# CAN485_1_0_0.net
KiCad netlist of a schematic drawn in EAGLE
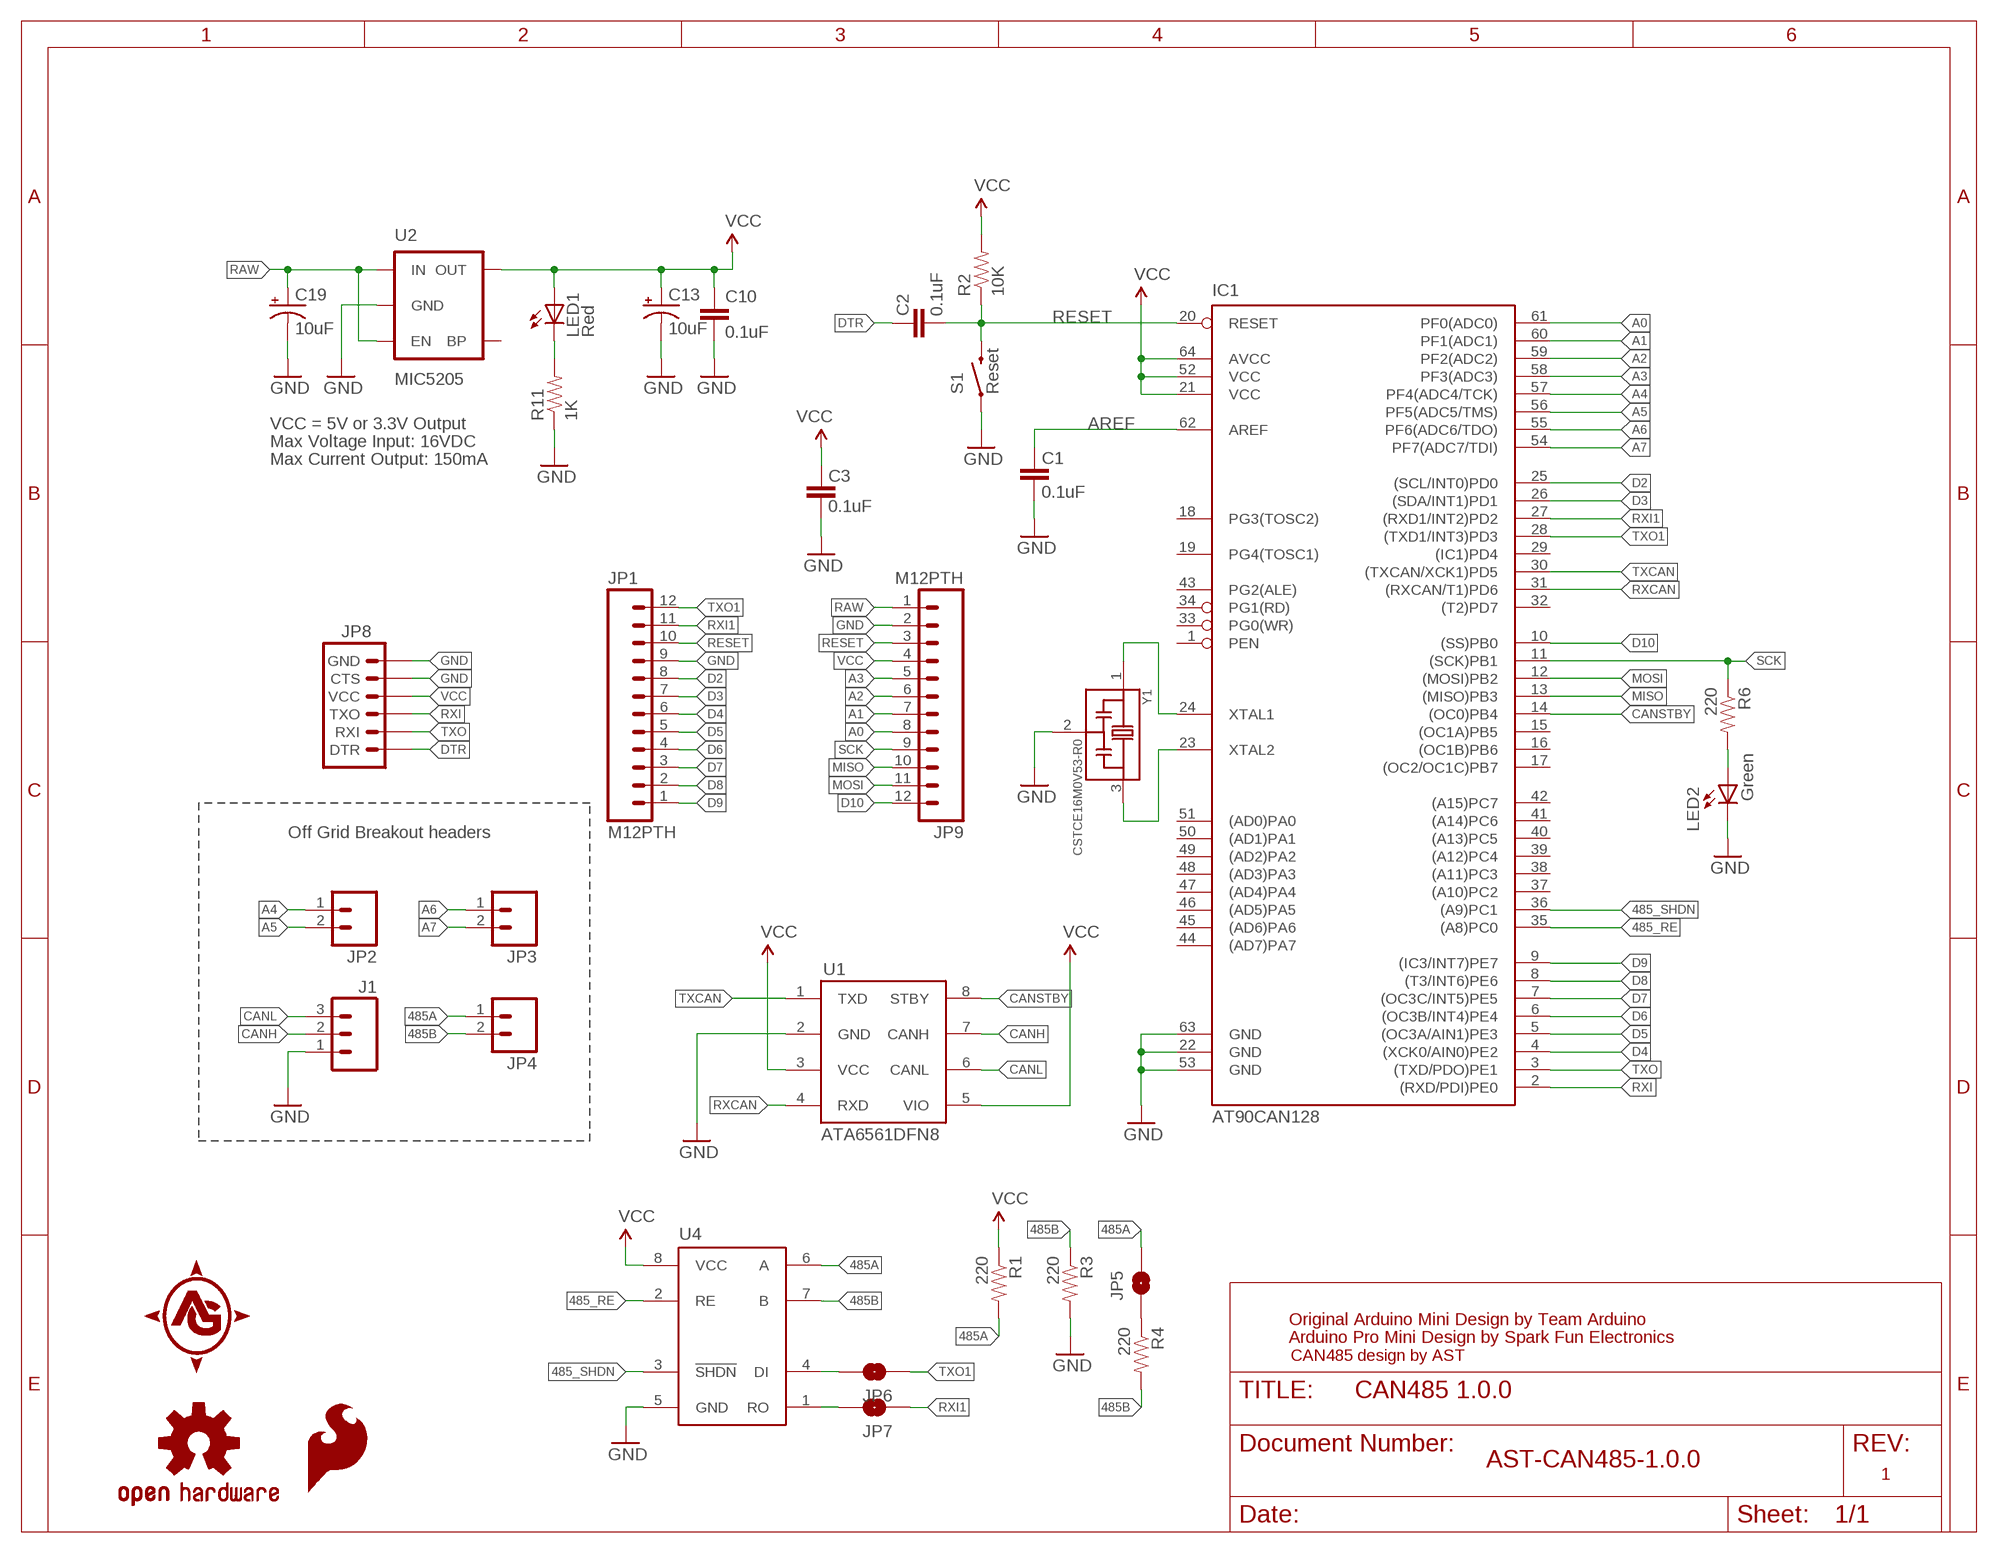
[diagram p0: schematic, sheet 1]

(export (version "E")
  (design (tool "Eeschema 10.0.6"))
  (components
    (comp (ref "C1")
      (value "0.1uF")
      (footprint "eagle-import:0402-CAP")
      (libsource (lib "eagle-import") (part "CAP0402-CAP"))
    )
    (comp (ref "C2")
      (value "0.1uF")
      (footprint "eagle-import:0402-CAP")
      (libsource (lib "eagle-import") (part "CAP0402-CAP"))
    )
    (comp (ref "C3")
      (value "0.1uF")
      (footprint "eagle-import:0402-CAP")
      (libsource (lib "eagle-import") (part "CAP0402-CAP"))
    )
    (comp (ref "C10")
      (value "0.1uF")
      (footprint "eagle-import:0402-CAP")
      (libsource (lib "eagle-import") (part "CAP0402-CAP"))
    )
    (comp (ref "C13")
      (value "10uF")
      (footprint "eagle-import:EIA3216")
      (libsource (lib "eagle-import") (part "CAP_POL1206"))
    )
    (comp (ref "C19")
      (value "10uF")
      (footprint "eagle-import:EIA3216")
      (libsource (lib "eagle-import") (part "CAP_POL1206"))
    )
    (comp (ref "IC1")
      (value "AT90CAN128")
      (footprint "eagle-import:MLF64")
      (fields (field (name "MPN") "ATMEGA64-16MU"))
      (libsource (lib "eagle-import") (part "MEGA64-M"))
    )
    (comp (ref "J1")
      (value "M03PTH")
      (footprint "eagle-import:1X03")
      (libsource (lib "eagle-import") (part "M03PTH"))
    )
    (comp (ref "JP1")
      (value "M12PTH")
      (footprint "eagle-import:1X12")
      (libsource (lib "eagle-import") (part "M12PTH"))
    )
    (comp (ref "JP2")
      (value "M02PTH")
      (footprint "eagle-import:1X02")
      (libsource (lib "eagle-import") (part "M02PTH"))
    )
    (comp (ref "JP3")
      (value "M02PTH")
      (footprint "eagle-import:1X02")
      (libsource (lib "eagle-import") (part "M02PTH"))
    )
    (comp (ref "JP4")
      (value "M02PTH")
      (footprint "eagle-import:1X02")
      (libsource (lib "eagle-import") (part "M02PTH"))
    )
    (comp (ref "JP5")
      (value "JUMPER-PAD-2-NO")
      (footprint "eagle-import:PAD-JUMPER-2-NO_NO_SILK")
      (libsource (lib "eagle-import") (part "JUMPER-PAD-2-NO"))
    )
    (comp (ref "JP6")
      (value "JUMPER-PAD-2-NO")
      (footprint "eagle-import:PAD-JUMPER-2-NO_NO_SILK")
      (libsource (lib "eagle-import") (part "JUMPER-PAD-2-NO"))
    )
    (comp (ref "JP7")
      (value "JUMPER-PAD-2-NO")
      (footprint "eagle-import:PAD-JUMPER-2-NO_NO_SILK")
      (libsource (lib "eagle-import") (part "JUMPER-PAD-2-NO"))
    )
    (comp (ref "JP8")
      (value "ARDUINO_SERIAL_PROGRAMPTH")
      (footprint "eagle-import:1X06")
      (libsource (lib "eagle-import") (part "ARDUINO_SERIAL_PROGRAMPTH"))
    )
    (comp (ref "JP9")
      (value "M12PTH")
      (footprint "eagle-import:1X12")
      (libsource (lib "eagle-import") (part "M12PTH"))
    )
    (comp (ref "LED1")
      (value "Red")
      (footprint "eagle-import:0603-LED-ALT1")
      (libsource (lib "eagle-import") (part "LED"))
    )
    (comp (ref "LED2")
      (value "Green")
      (footprint "eagle-import:0603-LED-ALT1")
      (libsource (lib "eagle-import") (part "LED"))
    )
    (comp (ref "LOGO1")
      (value "OSHW-LOGOMINI")
      (footprint "eagle-import:OSHW-LOGO-MINI")
      (libsource (lib "eagle-import") (part "OSHW-LOGOMINI"))
    )
    (comp (ref "LOGO2")
      (value "SFE_LOGO_FLAME0.05_INCH")
      (footprint "eagle-import:SFE_LOGO_FLAME_.05")
      (libsource (lib "eagle-import") (part "SFE_LOGO_FLAME0.05_INCH"))
    )
    (comp (ref "R1")
      (value "220")
      (footprint "eagle-import:0402-RES")
      (libsource (lib "eagle-import") (part "RESISTOR0402-RES"))
    )
    (comp (ref "R2")
      (value "10K")
      (footprint "eagle-import:0402-RES")
      (libsource (lib "eagle-import") (part "RESISTOR0402-RES"))
    )
    (comp (ref "R3")
      (value "220")
      (footprint "eagle-import:0402-RES")
      (libsource (lib "eagle-import") (part "RESISTOR0402-RES"))
    )
    (comp (ref "R4")
      (value "220")
      (footprint "eagle-import:0402-RES")
      (libsource (lib "eagle-import") (part "RESISTOR0402-RES"))
    )
    (comp (ref "R6")
      (value "220")
      (footprint "eagle-import:0402-RES")
      (libsource (lib "eagle-import") (part "RESISTOR0402-RES"))
    )
    (comp (ref "R11")
      (value "1K")
      (footprint "eagle-import:0402-RES")
      (libsource (lib "eagle-import") (part "RESISTOR0402-RES"))
    )
    (comp (ref "S1")
      (value "Reset")
      (footprint "eagle-import:TACTILE-SWITCH-1101NE")
      (libsource (lib "eagle-import") (part "SWITCH-MOMENTARY-2-SMD-1101NE"))
    )
    (comp (ref "U1")
      (value "ATA6561DFN8")
      (footprint "eagle-import:MSOP8")
      (libsource (lib "eagle-import") (part "ATA6561DFN8"))
    )
    (comp (ref "U2")
      (value "MIC5205")
      (footprint "eagle-import:SC70")
      (libsource (lib "eagle-import") (part "V_REG_LDOSMD2"))
    )
    (comp (ref "U4")
      (value "MAX13487SOIC")
      (footprint "eagle-import:MAX13487")
      (libsource (lib "eagle-import") (part "MAX13487SOIC"))
    )
    (comp (ref "Y1")
      (value "CSTCE16M0V53-R0")
      (footprint "eagle-import:OSC_CSTCE16M0V53-R0")
      (fields (field (name "MF") "Murata"))
      (libsource (lib "eagle-import") (part "CSTCE16M0V53-R0"))
    )
  )
  (nets
    (net (code "1") (name "/AREF") (class "Default")
      (node (ref "C1") (pin "2") (pinfunction "2_2") (pintype "passive"))
      (node (ref "IC1") (pin "62") (pinfunction "AREF_62") (pintype "passive"))
    )
    (net (code "2") (name "485A") (class "Default")
      (node (ref "JP4") (pin "1") (pinfunction "1_1") (pintype "passive"))
      (node (ref "JP5") (pin "2") (pinfunction "2_2") (pintype "passive"))
      (node (ref "R1") (pin "2") (pinfunction "2_2") (pintype "passive"))
      (node (ref "U4") (pin "6") (pinfunction "A_6") (pintype "bidirectional"))
    )
    (net (code "3") (name "485B") (class "Default")
      (node (ref "JP4") (pin "2") (pinfunction "2_2") (pintype "passive"))
      (node (ref "R3") (pin "1") (pinfunction "1_1") (pintype "passive"))
      (node (ref "R4") (pin "2") (pinfunction "2_2") (pintype "passive"))
      (node (ref "U4") (pin "7") (pinfunction "B_7") (pintype "bidirectional"))
    )
    (net (code "4") (name "485_RE") (class "Default")
      (node (ref "IC1") (pin "35") (pinfunction "(A8)PC0_35") (pintype "output"))
      (node (ref "U4") (pin "2") (pinfunction "RE_2") (pintype "bidirectional"))
    )
    (net (code "5") (name "485_SHDN") (class "Default")
      (node (ref "IC1") (pin "36") (pinfunction "(A9)PC1_36") (pintype "output"))
      (node (ref "U4") (pin "3") (pinfunction "~{SHDN}_3") (pintype "bidirectional"))
    )
    (net (code "6") (name "A0") (class "Default")
      (node (ref "IC1") (pin "61") (pinfunction "PF0(ADC0)_61") (pintype "input"))
      (node (ref "JP9") (pin "8") (pinfunction "8_8") (pintype "passive"))
    )
    (net (code "7") (name "A1") (class "Default")
      (node (ref "IC1") (pin "60") (pinfunction "PF1(ADC1)_60") (pintype "input"))
      (node (ref "JP9") (pin "7") (pinfunction "7_7") (pintype "passive"))
    )
    (net (code "8") (name "A2") (class "Default")
      (node (ref "IC1") (pin "59") (pinfunction "PF2(ADC2)_59") (pintype "input"))
      (node (ref "JP9") (pin "6") (pinfunction "6_6") (pintype "passive"))
    )
    (net (code "9") (name "A3") (class "Default")
      (node (ref "IC1") (pin "58") (pinfunction "PF3(ADC3)_58") (pintype "input"))
      (node (ref "JP9") (pin "5") (pinfunction "5_5") (pintype "passive"))
    )
    (net (code "10") (name "A4") (class "Default")
      (node (ref "IC1") (pin "57") (pinfunction "PF4(ADC4/TCK)_57") (pintype "input"))
      (node (ref "JP2") (pin "1") (pinfunction "1_1") (pintype "passive"))
    )
    (net (code "11") (name "A5") (class "Default")
      (node (ref "IC1") (pin "56") (pinfunction "PF5(ADC5/TMS)_56") (pintype "input"))
      (node (ref "JP2") (pin "2") (pinfunction "2_2") (pintype "passive"))
    )
    (net (code "12") (name "A6") (class "Default")
      (node (ref "IC1") (pin "55") (pinfunction "PF6(ADC6/TDO)_55") (pintype "input"))
      (node (ref "JP3") (pin "1") (pinfunction "1_1") (pintype "passive"))
    )
    (net (code "13") (name "A7") (class "Default")
      (node (ref "IC1") (pin "54") (pinfunction "PF7(ADC7/TDI)_54") (pintype "input"))
      (node (ref "JP3") (pin "2") (pinfunction "2_2") (pintype "passive"))
    )
    (net (code "14") (name "CANH") (class "Default")
      (node (ref "J1") (pin "2") (pinfunction "2_2") (pintype "passive"))
      (node (ref "U1") (pin "7") (pinfunction "CANH_7") (pintype "bidirectional"))
    )
    (net (code "15") (name "CANL") (class "Default")
      (node (ref "J1") (pin "3") (pinfunction "3_3") (pintype "passive"))
      (node (ref "U1") (pin "6") (pinfunction "CANL_6") (pintype "bidirectional"))
    )
    (net (code "16") (name "CANSTBY") (class "Default")
      (node (ref "IC1") (pin "14") (pinfunction "(OC0)PB4_14") (pintype "bidirectional"))
      (node (ref "U1") (pin "8") (pinfunction "STBY_8") (pintype "bidirectional"))
    )
    (net (code "17") (name "D2") (class "Default")
      (node (ref "IC1") (pin "25") (pinfunction "(SCL/INT0)PD0_25") (pintype "bidirectional"))
      (node (ref "JP1") (pin "8") (pinfunction "8_8") (pintype "passive"))
    )
    (net (code "18") (name "D3") (class "Default")
      (node (ref "IC1") (pin "26") (pinfunction "(SDA/INT1)PD1_26") (pintype "bidirectional"))
      (node (ref "JP1") (pin "7") (pinfunction "7_7") (pintype "passive"))
    )
    (net (code "19") (name "D4") (class "Default")
      (node (ref "IC1") (pin "4") (pinfunction "(XCK0/AIN0)PE2_4") (pintype "bidirectional"))
      (node (ref "JP1") (pin "6") (pinfunction "6_6") (pintype "passive"))
    )
    (net (code "20") (name "D5") (class "Default")
      (node (ref "IC1") (pin "5") (pinfunction "(OC3A/AIN1)PE3_5") (pintype "bidirectional"))
      (node (ref "JP1") (pin "5") (pinfunction "5_5") (pintype "passive"))
    )
    (net (code "21") (name "D6") (class "Default")
      (node (ref "IC1") (pin "6") (pinfunction "(OC3B/INT4)PE4_6") (pintype "bidirectional"))
      (node (ref "JP1") (pin "4") (pinfunction "4_4") (pintype "passive"))
    )
    (net (code "22") (name "D7") (class "Default")
      (node (ref "IC1") (pin "7") (pinfunction "(OC3C/INT5)PE5_7") (pintype "bidirectional"))
      (node (ref "JP1") (pin "3") (pinfunction "3_3") (pintype "passive"))
    )
    (net (code "23") (name "D8") (class "Default")
      (node (ref "IC1") (pin "8") (pinfunction "(T3/INT6)PE6_8") (pintype "bidirectional"))
      (node (ref "JP1") (pin "2") (pinfunction "2_2") (pintype "passive"))
    )
    (net (code "24") (name "D9") (class "Default")
      (node (ref "IC1") (pin "9") (pinfunction "(IC3/INT7)PE7_9") (pintype "bidirectional"))
      (node (ref "JP1") (pin "1") (pinfunction "1_1") (pintype "passive"))
    )
    (net (code "25") (name "D10") (class "Default")
      (node (ref "IC1") (pin "10") (pinfunction "(SS)PB0_10") (pintype "bidirectional"))
      (node (ref "JP9") (pin "12") (pinfunction "12_12") (pintype "passive"))
    )
    (net (code "26") (name "DTR") (class "Default")
      (node (ref "C2") (pin "2") (pinfunction "2_2") (pintype "passive"))
      (node (ref "JP8") (pin "1") (pinfunction "DTR_1") (pintype "passive"))
    )
    (net (code "27") (name "GND") (class "Default")
      (node (ref "C1") (pin "1") (pinfunction "1_1") (pintype "passive"))
      (node (ref "C10") (pin "2") (pinfunction "2_2") (pintype "passive"))
      (node (ref "C13") (pin "C") (pinfunction "-_C") (pintype "passive"))
      (node (ref "C19") (pin "C") (pinfunction "-_C") (pintype "passive"))
      (node (ref "C3") (pin "1") (pinfunction "1_1") (pintype "passive"))
      (node (ref "IC1") (pin "22") (pinfunction "GND_22") (pintype "power_in"))
      (node (ref "IC1") (pin "53") (pinfunction "GND_53") (pintype "power_in"))
      (node (ref "IC1") (pin "63") (pinfunction "GND_63") (pintype "power_in"))
      (node (ref "J1") (pin "1") (pinfunction "1_1") (pintype "passive"))
      (node (ref "JP1") (pin "9") (pinfunction "9_9") (pintype "passive"))
      (node (ref "JP8") (pin "5") (pinfunction "CTS_5") (pintype "passive"))
      (node (ref "JP8") (pin "6") (pinfunction "GND_6") (pintype "passive"))
      (node (ref "JP9") (pin "2") (pinfunction "2_2") (pintype "passive"))
      (node (ref "LED2") (pin "C") (pinfunction "C_C") (pintype "passive"))
      (node (ref "R11") (pin "1") (pinfunction "1_1") (pintype "passive"))
      (node (ref "R3") (pin "2") (pinfunction "2_2") (pintype "passive"))
      (node (ref "S1") (pin "P$1") (pinfunction "1_P$1") (pintype "passive"))
      (node (ref "U1") (pin "2") (pinfunction "GND_2") (pintype "power_in"))
      (node (ref "U2") (pin "2") (pinfunction "GND_2") (pintype "input"))
      (node (ref "U4") (pin "5") (pinfunction "GND_5") (pintype "power_in"))
      (node (ref "Y1") (pin "2") (pinfunction "2_2") (pintype "power_in"))
    )
    (net (code "28") (name "MISO") (class "Default")
      (node (ref "IC1") (pin "13") (pinfunction "(MISO)PB3_13") (pintype "bidirectional"))
      (node (ref "JP9") (pin "10") (pinfunction "10_10") (pintype "passive"))
    )
    (net (code "29") (name "MOSI") (class "Default")
      (node (ref "IC1") (pin "12") (pinfunction "(MOSI)PB2_12") (pintype "bidirectional"))
      (node (ref "JP9") (pin "11") (pinfunction "11_11") (pintype "passive"))
    )
    (net (code "30") (name "Net-(IC1-XTAL1)") (class "Default")
      (node (ref "IC1") (pin "24") (pinfunction "XTAL1_24") (pintype "bidirectional"))
      (node (ref "Y1") (pin "1") (pinfunction "1_1") (pintype "passive"))
    )
    (net (code "31") (name "Net-(IC1-XTAL2)") (class "Default")
      (node (ref "IC1") (pin "23") (pinfunction "XTAL2_23") (pintype "bidirectional"))
      (node (ref "Y1") (pin "3") (pinfunction "3_3") (pintype "passive"))
    )
    (net (code "32") (name "Net-(JP5-Pad1)") (class "Default")
      (node (ref "JP5") (pin "1") (pinfunction "1_1") (pintype "passive"))
      (node (ref "R4") (pin "1") (pinfunction "1_1") (pintype "passive"))
    )
    (net (code "33") (name "Net-(LED1-PadC)") (class "Default")
      (node (ref "LED1") (pin "C") (pinfunction "C_C") (pintype "passive"))
      (node (ref "R11") (pin "2") (pinfunction "2_2") (pintype "passive"))
    )
    (net (code "34") (name "Net-(LED2-PadA)") (class "Default")
      (node (ref "LED2") (pin "A") (pinfunction "A_A") (pintype "passive"))
      (node (ref "R6") (pin "2") (pinfunction "2_2") (pintype "passive"))
    )
    (net (code "35") (name "Net-(U4-DI)") (class "Default")
      (node (ref "JP6") (pin "2") (pinfunction "2_2") (pintype "passive"))
      (node (ref "U4") (pin "4") (pinfunction "DI_4") (pintype "input"))
    )
    (net (code "36") (name "Net-(U4-RO)") (class "Default")
      (node (ref "JP7") (pin "2") (pinfunction "2_2") (pintype "passive"))
      (node (ref "U4") (pin "1") (pinfunction "RO_1") (pintype "output"))
    )
    (net (code "37") (name "RAW") (class "Default")
      (node (ref "C19") (pin "A") (pinfunction "+_A") (pintype "passive"))
      (node (ref "JP9") (pin "1") (pinfunction "1_1") (pintype "passive"))
      (node (ref "U2") (pin "1") (pinfunction "IN_1") (pintype "input"))
      (node (ref "U2") (pin "3") (pinfunction "EN_3") (pintype "input"))
    )
    (net (code "38") (name "RESET") (class "Default")
      (node (ref "C2") (pin "1") (pinfunction "1_1") (pintype "passive"))
      (node (ref "IC1") (pin "20") (pinfunction "RESET_20") (pintype "input"))
      (node (ref "JP1") (pin "10") (pinfunction "10_10") (pintype "passive"))
      (node (ref "JP9") (pin "3") (pinfunction "3_3") (pintype "passive"))
      (node (ref "R2") (pin "1") (pinfunction "1_1") (pintype "passive"))
      (node (ref "S1") (pin "P$2") (pinfunction "2_P$2") (pintype "passive"))
    )
    (net (code "39") (name "RXCAN") (class "Default")
      (node (ref "IC1") (pin "31") (pinfunction "(RXCAN/T1)PD6_31") (pintype "bidirectional"))
      (node (ref "U1") (pin "4") (pinfunction "RXD_4") (pintype "bidirectional"))
    )
    (net (code "40") (name "RXI") (class "Default")
      (node (ref "IC1") (pin "2") (pinfunction "(RXD/PDI)PE0_2") (pintype "bidirectional"))
      (node (ref "JP8") (pin "3") (pinfunction "TXO_3") (pintype "passive"))
    )
    (net (code "41") (name "RXI1") (class "Default")
      (node (ref "IC1") (pin "27") (pinfunction "(RXD1/INT2)PD2_27") (pintype "bidirectional"))
      (node (ref "JP1") (pin "11") (pinfunction "11_11") (pintype "passive"))
      (node (ref "JP7") (pin "1") (pinfunction "1_1") (pintype "passive"))
    )
    (net (code "42") (name "SCK") (class "Default")
      (node (ref "IC1") (pin "11") (pinfunction "(SCK)PB1_11") (pintype "bidirectional"))
      (node (ref "JP9") (pin "9") (pinfunction "9_9") (pintype "passive"))
      (node (ref "R6") (pin "1") (pinfunction "1_1") (pintype "passive"))
    )
    (net (code "43") (name "TXCAN") (class "Default")
      (node (ref "IC1") (pin "30") (pinfunction "(TXCAN/XCK1)PD5_30") (pintype "bidirectional"))
      (node (ref "U1") (pin "1") (pinfunction "TXD_1") (pintype "bidirectional"))
    )
    (net (code "44") (name "TXO") (class "Default")
      (node (ref "IC1") (pin "3") (pinfunction "(TXD/PDO)PE1_3") (pintype "bidirectional"))
      (node (ref "JP8") (pin "2") (pinfunction "RXI_2") (pintype "passive"))
    )
    (net (code "45") (name "TXO1") (class "Default")
      (node (ref "IC1") (pin "28") (pinfunction "(TXD1/INT3)PD3_28") (pintype "bidirectional"))
      (node (ref "JP1") (pin "12") (pinfunction "12_12") (pintype "passive"))
      (node (ref "JP6") (pin "1") (pinfunction "1_1") (pintype "passive"))
    )
    (net (code "46") (name "VCC") (class "Default")
      (node (ref "C10") (pin "1") (pinfunction "1_1") (pintype "passive"))
      (node (ref "C13") (pin "A") (pinfunction "+_A") (pintype "passive"))
      (node (ref "C3") (pin "2") (pinfunction "2_2") (pintype "passive"))
      (node (ref "IC1") (pin "21") (pinfunction "VCC_21") (pintype "power_in"))
      (node (ref "IC1") (pin "52") (pinfunction "VCC_52") (pintype "power_in"))
      (node (ref "IC1") (pin "64") (pinfunction "AVCC_64") (pintype "power_in"))
      (node (ref "JP8") (pin "4") (pinfunction "VCC_4") (pintype "passive"))
      (node (ref "JP9") (pin "4") (pinfunction "4_4") (pintype "passive"))
      (node (ref "LED1") (pin "A") (pinfunction "A_A") (pintype "passive"))
      (node (ref "R1") (pin "1") (pinfunction "1_1") (pintype "passive"))
      (node (ref "R2") (pin "2") (pinfunction "2_2") (pintype "passive"))
      (node (ref "U1") (pin "3") (pinfunction "VCC_3") (pintype "power_in"))
      (node (ref "U1") (pin "5") (pinfunction "VIO_5") (pintype "bidirectional"))
      (node (ref "U2") (pin "5") (pinfunction "OUT_5") (pintype "passive"))
      (node (ref "U4") (pin "8") (pinfunction "VCC_8") (pintype "power_in"))
    )
    (net (code "47") (name "unconnected-(IC1-(A10)PC2-Pad37)") (class "Default")
      (node (ref "IC1") (pin "37") (pinfunction "(A10)PC2_37") (pintype "output"))
    )
    (net (code "48") (name "unconnected-(IC1-(A11)PC3-Pad38)") (class "Default")
      (node (ref "IC1") (pin "38") (pinfunction "(A11)PC3_38") (pintype "output"))
    )
    (net (code "49") (name "unconnected-(IC1-(A12)PC4-Pad39)") (class "Default")
      (node (ref "IC1") (pin "39") (pinfunction "(A12)PC4_39") (pintype "output"))
    )
    (net (code "50") (name "unconnected-(IC1-(A13)PC5-Pad40)") (class "Default")
      (node (ref "IC1") (pin "40") (pinfunction "(A13)PC5_40") (pintype "output"))
    )
    (net (code "51") (name "unconnected-(IC1-(A14)PC6-Pad41)") (class "Default")
      (node (ref "IC1") (pin "41") (pinfunction "(A14)PC6_41") (pintype "output"))
    )
    (net (code "52") (name "unconnected-(IC1-(A15)PC7-Pad42)") (class "Default")
      (node (ref "IC1") (pin "42") (pinfunction "(A15)PC7_42") (pintype "output"))
    )
    (net (code "53") (name "unconnected-(IC1-(AD0)PA0-Pad51)") (class "Default")
      (node (ref "IC1") (pin "51") (pinfunction "(AD0)PA0_51") (pintype "bidirectional"))
    )
    (net (code "54") (name "unconnected-(IC1-(AD1)PA1-Pad50)") (class "Default")
      (node (ref "IC1") (pin "50") (pinfunction "(AD1)PA1_50") (pintype "bidirectional"))
    )
    (net (code "55") (name "unconnected-(IC1-(AD2)PA2-Pad49)") (class "Default")
      (node (ref "IC1") (pin "49") (pinfunction "(AD2)PA2_49") (pintype "bidirectional"))
    )
    (net (code "56") (name "unconnected-(IC1-(AD3)PA3-Pad48)") (class "Default")
      (node (ref "IC1") (pin "48") (pinfunction "(AD3)PA3_48") (pintype "bidirectional"))
    )
    (net (code "57") (name "unconnected-(IC1-(AD4)PA4-Pad47)") (class "Default")
      (node (ref "IC1") (pin "47") (pinfunction "(AD4)PA4_47") (pintype "bidirectional"))
    )
    (net (code "58") (name "unconnected-(IC1-(AD5)PA5-Pad46)") (class "Default")
      (node (ref "IC1") (pin "46") (pinfunction "(AD5)PA5_46") (pintype "bidirectional"))
    )
    (net (code "59") (name "unconnected-(IC1-(AD6)PA6-Pad45)") (class "Default")
      (node (ref "IC1") (pin "45") (pinfunction "(AD6)PA6_45") (pintype "bidirectional"))
    )
    (net (code "60") (name "unconnected-(IC1-(AD7)PA7-Pad44)") (class "Default")
      (node (ref "IC1") (pin "44") (pinfunction "(AD7)PA7_44") (pintype "bidirectional"))
    )
    (net (code "61") (name "unconnected-(IC1-(IC1)PD4-Pad29)") (class "Default")
      (node (ref "IC1") (pin "29") (pinfunction "(IC1)PD4_29") (pintype "bidirectional"))
    )
    (net (code "62") (name "unconnected-(IC1-(OC1A)PB5-Pad15)") (class "Default")
      (node (ref "IC1") (pin "15") (pinfunction "(OC1A)PB5_15") (pintype "bidirectional"))
    )
    (net (code "63") (name "unconnected-(IC1-(OC1B)PB6-Pad16)") (class "Default")
      (node (ref "IC1") (pin "16") (pinfunction "(OC1B)PB6_16") (pintype "bidirectional"))
    )
    (net (code "64") (name "unconnected-(IC1-(OC2{slash}OC1C)PB7-Pad17)") (class "Default")
      (node (ref "IC1") (pin "17") (pinfunction "(OC2/OC1C)PB7_17") (pintype "bidirectional"))
    )
    (net (code "65") (name "unconnected-(IC1-(T2)PD7-Pad32)") (class "Default")
      (node (ref "IC1") (pin "32") (pinfunction "(T2)PD7_32") (pintype "bidirectional"))
    )
    (net (code "66") (name "unconnected-(IC1-PEN-Pad1)") (class "Default")
      (node (ref "IC1") (pin "1") (pinfunction "PEN_1") (pintype "input"))
    )
    (net (code "67") (name "unconnected-(IC1-PG0(WR)-Pad33)") (class "Default")
      (node (ref "IC1") (pin "33") (pinfunction "PG0(WR)_33") (pintype "bidirectional"))
    )
    (net (code "68") (name "unconnected-(IC1-PG1(RD)-Pad34)") (class "Default")
      (node (ref "IC1") (pin "34") (pinfunction "PG1(RD)_34") (pintype "bidirectional"))
    )
    (net (code "69") (name "unconnected-(IC1-PG2(ALE)-Pad43)") (class "Default")
      (node (ref "IC1") (pin "43") (pinfunction "PG2(ALE)_43") (pintype "bidirectional"))
    )
    (net (code "70") (name "unconnected-(IC1-PG3(TOSC2)-Pad18)") (class "Default")
      (node (ref "IC1") (pin "18") (pinfunction "PG3(TOSC2)_18") (pintype "bidirectional"))
    )
    (net (code "71") (name "unconnected-(IC1-PG4(TOSC1)-Pad19)") (class "Default")
      (node (ref "IC1") (pin "19") (pinfunction "PG4(TOSC1)_19") (pintype "bidirectional"))
    )
    (net (code "72") (name "unconnected-(U2-BP-Pad4)") (class "Default")
      (node (ref "U2") (pin "4") (pinfunction "BP_4") (pintype "input"))
    )
  )
)
